# SCC.net
KiCad netlist of a schematic drawn in Altium Designer
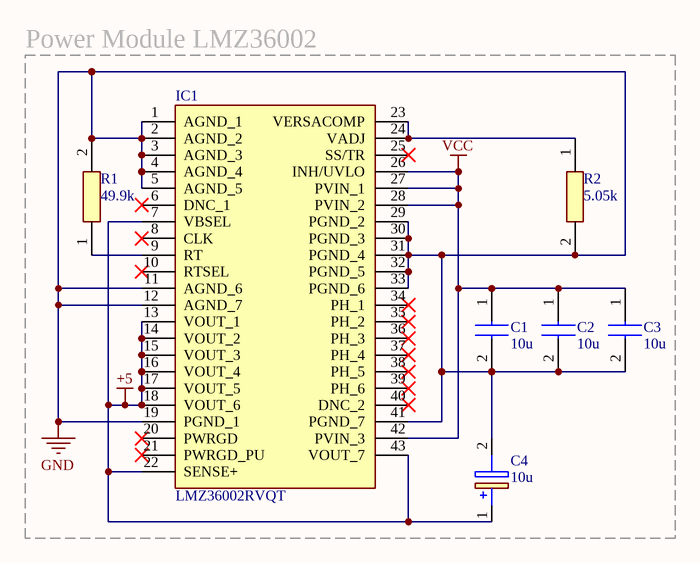
[diagram p0: SCC.SchDoc]

(export (version "E")
  (design (tool "Eeschema 10.0.6"))
  (components
    (comp (ref "C1")
      (value "10u")
      (footprint "RcMPPTLib:CAPC3225X280N")
      (description "Capacitor")
      (fields (field (name "MANUFACTURER_PART_NUMBER") "CL32B106KMVNNWE"))
      (libsource (lib "RcMPPTLib") (part "CL32B106KMVNNWE"))
    )
    (comp (ref "C2")
      (value "10u")
      (footprint "RcMPPTLib:CAPC3225X280N")
      (description "Capacitor")
      (fields (field (name "MANUFACTURER_PART_NUMBER") "CL32B106KMVNNWE"))
      (libsource (lib "RcMPPTLib") (part "CL32B106KMVNNWE"))
    )
    (comp (ref "C3")
      (value "10u")
      (footprint "RcMPPTLib:CAPC3225X280N")
      (description "Capacitor")
      (fields (field (name "MANUFACTURER_PART_NUMBER") "CL32B106KMVNNWE"))
      (libsource (lib "RcMPPTLib") (part "CL32B106KMVNNWE"))
    )
    (comp (ref "C4")
      (value "10u")
      (footprint "RcMPPTLib:CAPPM3528X210N")
      (description "Capacitor Polarised")
      (fields
        (field (name "MANUFACTURER_PART_NUMBER") "TCJB106M025R0100")
        (field (name "MOUSER PART NUMBER") "581-TCJB106M025R")
      )
      (libsource (lib "RcMPPTLib") (part "TCJB106M025R0100"))
    )
    (comp (ref "IC1")
      (value "LMZ36002RVQT")
      (footprint "LMZ36002RVQR")
      (description "Integrated Circuit")
      (fields (field (name "MOUSER PART NUMBER") "595-LMZ36002RVQT"))
      (libsource (lib "RcMPPTLib") (part "LMZ36002RVQT"))
    )
    (comp (ref "R1")
      (value "49.9k")
      (footprint "RcMPPTLib:R0805")
      (description "Resistor")
      (fields
        (field (name "MANUFACTURER_PART_NUMBER") "ERJ-6ENF4992V")
        (field (name "MOUSER PART NUMBER") "667-ERJ-6ENF4992V")
      )
      (libsource (lib "RcMPPTLib") (part "ERJ-6ENF4992V"))
    )
    (comp (ref "R2")
      (value "5.05k")
      (footprint "R0805")
      (description "Resistor")
      (fields
        (field (name "MANUFACTURER_PART_NUMBER") "RT0805BRD075K05L")
        (field (name "MOUSER PART NUMBER") "603-RT0805BRD075K05L")
      )
      (libsource (lib "RcMPPTLib") (part "RT0805BRD075K05L"))
    )
  )
  (nets
    (net (code "1") (name "+5") (class "Default")
      (node (ref "C4") (pin "1") (pinfunction "+_1") (pintype "passive"))
      (node (ref "IC1") (pin "13") (pinfunction "VOUT_1_13") (pintype "passive"))
      (node (ref "IC1") (pin "14") (pinfunction "VOUT_2_14") (pintype "passive"))
      (node (ref "IC1") (pin "15") (pinfunction "VOUT_3_15") (pintype "passive"))
      (node (ref "IC1") (pin "16") (pinfunction "VOUT_4_16") (pintype "passive"))
      (node (ref "IC1") (pin "17") (pinfunction "VOUT_5_17") (pintype "passive"))
      (node (ref "IC1") (pin "18") (pinfunction "VOUT_6_18") (pintype "passive"))
      (node (ref "IC1") (pin "22") (pinfunction "SENSE+_22") (pintype "passive"))
      (node (ref "IC1") (pin "43") (pinfunction "VOUT_7_43") (pintype "passive"))
      (node (ref "IC1") (pin "7") (pinfunction "VBSEL_7") (pintype "passive"))
    )
    (net (code "2") (name "GND") (class "Default")
      (node (ref "C1") (pin "2") (pinfunction "2_2") (pintype "passive"))
      (node (ref "C2") (pin "2") (pinfunction "2_2") (pintype "passive"))
      (node (ref "C3") (pin "2") (pinfunction "2_2") (pintype "passive"))
      (node (ref "C4") (pin "2") (pinfunction "-_2") (pintype "passive"))
      (node (ref "IC1") (pin "1") (pinfunction "AGND_1_1") (pintype "passive"))
      (node (ref "IC1") (pin "11") (pinfunction "AGND_6_11") (pintype "passive"))
      (node (ref "IC1") (pin "12") (pinfunction "AGND_7_12") (pintype "passive"))
      (node (ref "IC1") (pin "19") (pinfunction "PGND_1_19") (pintype "passive"))
      (node (ref "IC1") (pin "2") (pinfunction "AGND_2_2") (pintype "passive"))
      (node (ref "IC1") (pin "29") (pinfunction "PGND_2_29") (pintype "passive"))
      (node (ref "IC1") (pin "3") (pinfunction "AGND_3_3") (pintype "passive"))
      (node (ref "IC1") (pin "30") (pinfunction "PGND_3_30") (pintype "passive"))
      (node (ref "IC1") (pin "31") (pinfunction "PGND_4_31") (pintype "passive"))
      (node (ref "IC1") (pin "32") (pinfunction "PGND_5_32") (pintype "passive"))
      (node (ref "IC1") (pin "33") (pinfunction "PGND_6_33") (pintype "passive"))
      (node (ref "IC1") (pin "4") (pinfunction "AGND_4_4") (pintype "passive"))
      (node (ref "IC1") (pin "41") (pinfunction "PGND_7_41") (pintype "passive"))
      (node (ref "IC1") (pin "5") (pinfunction "AGND_5_5") (pintype "passive"))
      (node (ref "R1") (pin "2") (pinfunction "2_2") (pintype "passive"))
      (node (ref "R2") (pin "2") (pinfunction "2_2") (pintype "passive"))
    )
    (net (code "3") (name "Net-(IC1-RT)") (class "Default")
      (node (ref "IC1") (pin "9") (pinfunction "RT_9") (pintype "passive"))
      (node (ref "R1") (pin "1") (pinfunction "1_1") (pintype "passive"))
    )
    (net (code "4") (name "Net-(IC1-VADJ)") (class "Default")
      (node (ref "IC1") (pin "23") (pinfunction "VERSACOMP_23") (pintype "passive"))
      (node (ref "IC1") (pin "24") (pinfunction "VADJ_24") (pintype "passive"))
      (node (ref "R2") (pin "1") (pinfunction "1_1") (pintype "passive"))
    )
    (net (code "5") (name "VCC") (class "Default")
      (node (ref "C1") (pin "1") (pinfunction "1_1") (pintype "passive"))
      (node (ref "C2") (pin "1") (pinfunction "1_1") (pintype "passive"))
      (node (ref "C3") (pin "1") (pinfunction "1_1") (pintype "passive"))
      (node (ref "IC1") (pin "26") (pinfunction "INH/UVLO_26") (pintype "passive"))
      (node (ref "IC1") (pin "27") (pinfunction "PVIN_1_27") (pintype "passive"))
      (node (ref "IC1") (pin "28") (pinfunction "PVIN_2_28") (pintype "passive"))
      (node (ref "IC1") (pin "42") (pinfunction "PVIN_3_42") (pintype "passive"))
    )
    (net (code "6") (name "unconnected-(IC1-CLK-Pad8)") (class "Default")
      (node (ref "IC1") (pin "8") (pinfunction "CLK_8") (pintype "passive+no_connect"))
    )
    (net (code "7") (name "unconnected-(IC1-DNC_1-Pad6)") (class "Default")
      (node (ref "IC1") (pin "6") (pinfunction "DNC_1_6") (pintype "passive+no_connect"))
    )
    (net (code "8") (name "unconnected-(IC1-DNC_2-Pad40)") (class "Default")
      (node (ref "IC1") (pin "40") (pinfunction "DNC_2_40") (pintype "passive+no_connect"))
    )
    (net (code "9") (name "unconnected-(IC1-PH_1-Pad34)") (class "Default")
      (node (ref "IC1") (pin "34") (pinfunction "PH_1_34") (pintype "passive+no_connect"))
    )
    (net (code "10") (name "unconnected-(IC1-PH_2-Pad35)") (class "Default")
      (node (ref "IC1") (pin "35") (pinfunction "PH_2_35") (pintype "passive+no_connect"))
    )
    (net (code "11") (name "unconnected-(IC1-PH_3-Pad36)") (class "Default")
      (node (ref "IC1") (pin "36") (pinfunction "PH_3_36") (pintype "passive+no_connect"))
    )
    (net (code "12") (name "unconnected-(IC1-PH_4-Pad37)") (class "Default")
      (node (ref "IC1") (pin "37") (pinfunction "PH_4_37") (pintype "passive+no_connect"))
    )
    (net (code "13") (name "unconnected-(IC1-PH_5-Pad38)") (class "Default")
      (node (ref "IC1") (pin "38") (pinfunction "PH_5_38") (pintype "passive+no_connect"))
    )
    (net (code "14") (name "unconnected-(IC1-PH_6-Pad39)") (class "Default")
      (node (ref "IC1") (pin "39") (pinfunction "PH_6_39") (pintype "passive+no_connect"))
    )
    (net (code "15") (name "unconnected-(IC1-PWRGD-Pad20)") (class "Default")
      (node (ref "IC1") (pin "20") (pinfunction "PWRGD_20") (pintype "passive+no_connect"))
    )
    (net (code "16") (name "unconnected-(IC1-PWRGD_PU-Pad21)") (class "Default")
      (node (ref "IC1") (pin "21") (pinfunction "PWRGD_PU_21") (pintype "passive+no_connect"))
    )
    (net (code "17") (name "unconnected-(IC1-RTSEL-Pad10)") (class "Default")
      (node (ref "IC1") (pin "10") (pinfunction "RTSEL_10") (pintype "passive+no_connect"))
    )
    (net (code "18") (name "unconnected-(IC1-SS{slash}TR-Pad25)") (class "Default")
      (node (ref "IC1") (pin "25") (pinfunction "SS/TR_25") (pintype "passive+no_connect"))
    )
  )
)
